# wifi.net
KiCad netlist of a schematic drawn in Altium Designer
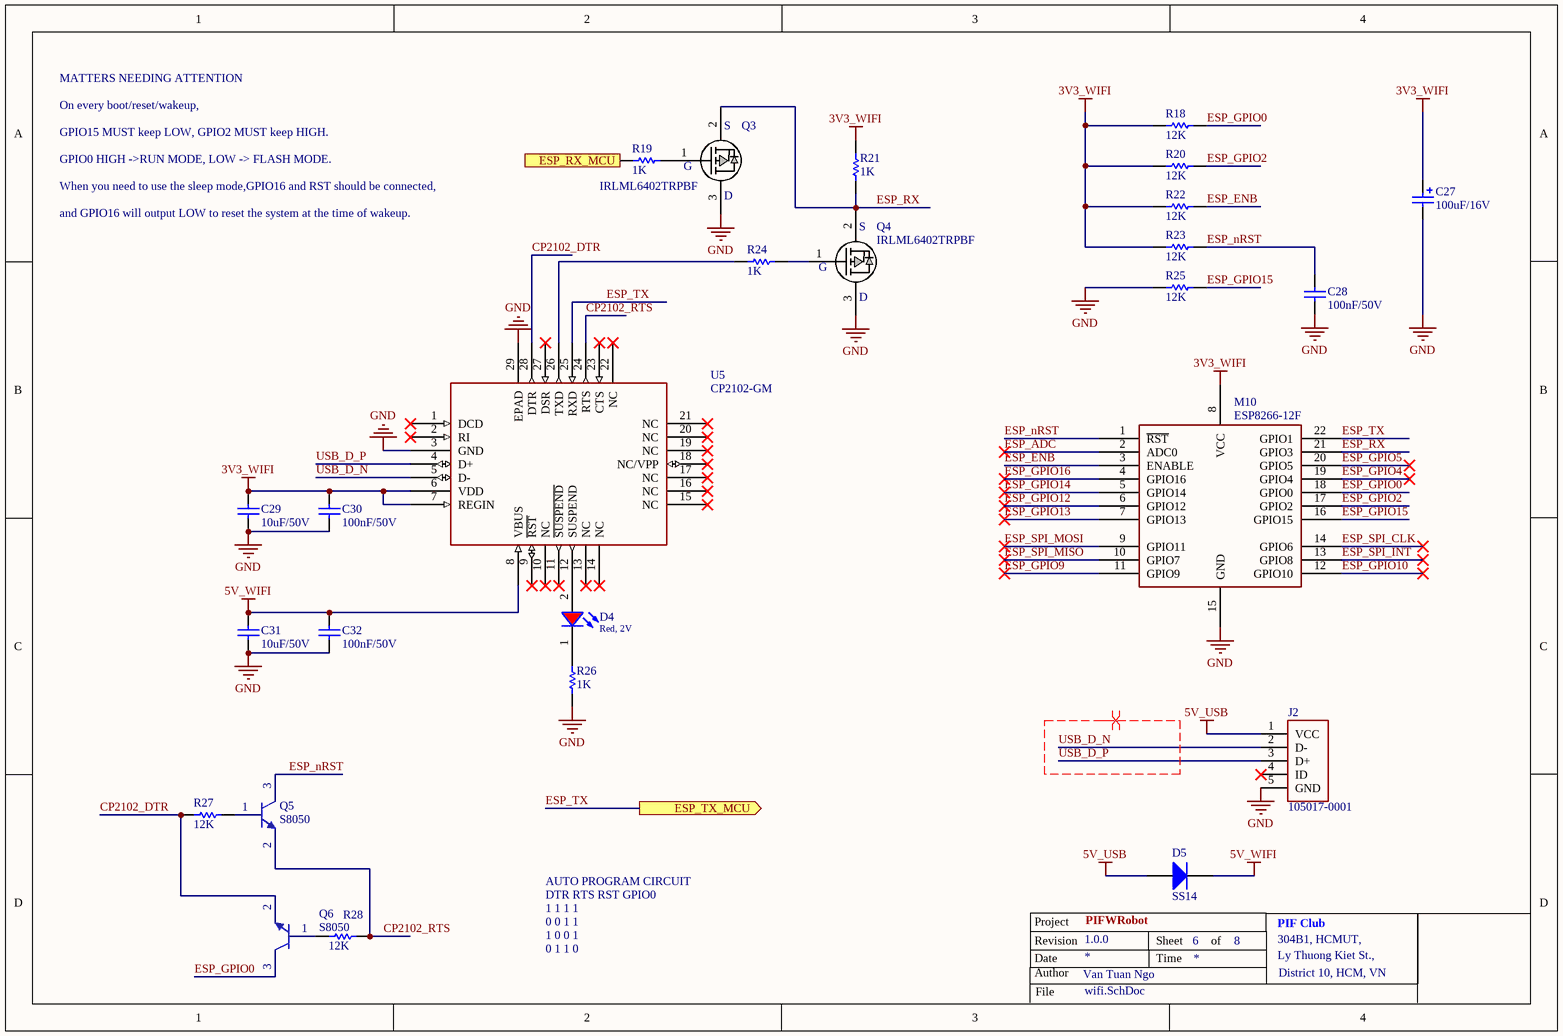
[diagram p0: wifi.SchDoc]

(export (version "E")
  (design (tool "Eeschema 10.0.6"))
  (components
    (comp (ref "C27")
      (value "100uF/16V")
      (footprint "CAP_SM_TAN")
      (fields
        (field (name "MANUFACTURER") "Nichicon")
        (field (name "MANUFACTURER PART NUMBER") "UWX1C101MCL1GB")
        (field (name "Comment") "TAJB107M006RNJ")
      )
      (libsource (lib "Capacitor") (part "Cap-Tan-100uF-16V"))
    )
    (comp (ref "C28")
      (value "100nF/50V")
      (footprint "CAP-SM-0805")
      (description "CAP CER 0.1UF 50V Y5V 0805")
      (fields
        (field (name "MANUFACTURER") "Samsung Electro-Mechanics")
        (field (name "MANUFACTURER PART NUMBER") "CL21F104ZBCNNNC")
      )
      (libsource (lib "Capacitor") (part "Cap-100nF-50V-0805"))
    )
    (comp (ref "C29")
      (value "10uF/50V")
      (footprint "CAP-SM-0805")
      (description "CAP CER 10UF 50V X5R 0805")
      (fields
        (field (name "MANUFACTURER") "Yageo")
        (field (name "MANUFACTURER PART NUMBER") "CC0805KKX5R9BB106")
      )
      (libsource (lib "Capacitor") (part "Cap-10uF-50V-0805"))
    )
    (comp (ref "C30")
      (value "100nF/50V")
      (footprint "CAP-SM-0805")
      (description "CAP CER 0.1UF 50V Y5V 0805")
      (fields
        (field (name "MANUFACTURER") "Samsung Electro-Mechanics")
        (field (name "MANUFACTURER PART NUMBER") "CL21F104ZBCNNNC")
      )
      (libsource (lib "Capacitor") (part "Cap-100nF-50V-0805"))
    )
    (comp (ref "C31")
      (value "10uF/50V")
      (footprint "CAP-SM-0805")
      (description "CAP CER 10UF 50V X5R 0805")
      (fields
        (field (name "MANUFACTURER") "Yageo")
        (field (name "MANUFACTURER PART NUMBER") "CC0805KKX5R9BB106")
      )
      (libsource (lib "Capacitor") (part "Cap-10uF-50V-0805"))
    )
    (comp (ref "C32")
      (value "100nF/50V")
      (footprint "CAP-SM-0805")
      (description "CAP CER 0.1UF 50V Y5V 0805")
      (fields
        (field (name "MANUFACTURER") "Samsung Electro-Mechanics")
        (field (name "MANUFACTURER PART NUMBER") "CL21F104ZBCNNNC")
      )
      (libsource (lib "Capacitor") (part "Cap-100nF-50V-0805"))
    )
    (comp (ref "D4")
      (value "Red, 2V")
      (footprint "WL-SMCW_0805")
      (description "WL-SMCW SMT Mono-color Chip LED Waterclear, size 0805, Red, 2V, 140deg")
      (fields
        (field (name "PART NUMBER") "150080RS75000")
        (field (name "LOCAL SUPPLIER PARTNUMBER") "x")
        (field (name "PUBLISHER") "Wurth Elektronik")
      )
      (libsource (lib "LED") (part "0805-Red"))
    )
    (comp (ref "D5")
      (value "SS14")
      (footprint "SS14")
      (description "DIODE SCHOTTKY 40V 1A SMA")
      (fields (field (name "MANUFACTURER") "ON Semiconductor"))
      (libsource (lib "Diode") (part "Diode-SS14"))
    )
    (comp (ref "J2")
      (value "105017-0001")
      (footprint "CONN_105017-0001")
      (description "CONN RCPT USB2.0 MICRO B SMD R/A")
      (fields
        (field (name "LOCAL SUPPLIER PART NUMBER") "x")
        (field (name "COPYRIGHT") "Copyright (C) 2018 Accelerated Designs. All rights reserved")
      )
      (libsource (lib "Header-Connector") (part "105017-0001"))
    )
    (comp (ref "M10")
      (value "ESP8266-12F")
      (footprint "ESP8266-12F")
      (fields (field (name "LOCAL SUPPLIER PART NUMBER") "x"))
      (libsource (lib "PIFWRobot") (part "ESP8266-12F"))
    )
    (comp (ref "Q3")
      (value "IRLML6402TRPBF")
      (footprint "SOT23_NEX")
      (description "P-Channel 20V 3.7A (Ta) 1.3W (Ta) Surface Mount Micro3™/SOT-23")
      (libsource (lib "MOSFET") (part "IRLML6402TRPBF"))
    )
    (comp (ref "Q4")
      (value "IRLML6402TRPBF")
      (footprint "SOT23_NEX")
      (description "P-Channel 20V 3.7A (Ta) 1.3W (Ta) Surface Mount Micro3™/SOT-23")
      (libsource (lib "MOSFET") (part "IRLML6402TRPBF"))
    )
    (comp (ref "Q5") (value "S8050") (footprint "SOT23_NEX") (libsource (lib "BJT") (part "S8050")))
    (comp (ref "Q6") (value "S8050") (footprint "SOT23_NEX") (libsource (lib "BJT") (part "S8050")))
    (comp (ref "R18")
      (value "12K")
      (footprint "Resistor:RES-SM-0805")
      (description "RES 12 KOHM JUMPER 0805")
      (fields
        (field (name "MANUFACTURER") "Vishay Thin Film")
        (field (name "MANUFACTURER PART NUMBER") "PAT0805E3121BST1")
      )
      (libsource (lib "Resistor") (part "Res-12K-0805"))
    )
    (comp (ref "R19")
      (value "1K")
      (footprint "Resistor:RES-SM-0805")
      (description "RES 1K OHM 1% 1/4W 0805")
      (fields
        (field (name "MANUFACTURER") "Stackpole Electronics Inc")
        (field (name "MANUFACTURER PART NUMBER") "RNCP0805FTD1K00")
      )
      (libsource (lib "Resistor") (part "Res-1K-0805"))
    )
    (comp (ref "R20")
      (value "12K")
      (footprint "Resistor:RES-SM-0805")
      (description "RES 12 KOHM JUMPER 0805")
      (fields
        (field (name "MANUFACTURER") "Vishay Thin Film")
        (field (name "MANUFACTURER PART NUMBER") "PAT0805E3121BST1")
      )
      (libsource (lib "Resistor") (part "Res-12K-0805"))
    )
    (comp (ref "R21")
      (value "1K")
      (footprint "Resistor:RES-SM-0805")
      (description "RES 1K OHM 1% 1/4W 0805")
      (fields
        (field (name "MANUFACTURER") "Stackpole Electronics Inc")
        (field (name "MANUFACTURER PART NUMBER") "RNCP0805FTD1K00")
      )
      (libsource (lib "Resistor") (part "Res-1K-0805"))
    )
    (comp (ref "R22")
      (value "12K")
      (footprint "Resistor:RES-SM-0805")
      (description "RES 12 KOHM JUMPER 0805")
      (fields
        (field (name "MANUFACTURER") "Vishay Thin Film")
        (field (name "MANUFACTURER PART NUMBER") "PAT0805E3121BST1")
      )
      (libsource (lib "Resistor") (part "Res-12K-0805"))
    )
    (comp (ref "R23")
      (value "12K")
      (footprint "Resistor:RES-SM-0805")
      (description "RES 12 KOHM JUMPER 0805")
      (fields
        (field (name "MANUFACTURER") "Vishay Thin Film")
        (field (name "MANUFACTURER PART NUMBER") "PAT0805E3121BST1")
      )
      (libsource (lib "Resistor") (part "Res-12K-0805"))
    )
    (comp (ref "R24")
      (value "1K")
      (footprint "Resistor:RES-SM-0805")
      (description "RES 1K OHM 1% 1/4W 0805")
      (fields
        (field (name "MANUFACTURER") "Stackpole Electronics Inc")
        (field (name "MANUFACTURER PART NUMBER") "RNCP0805FTD1K00")
      )
      (libsource (lib "Resistor") (part "Res-1K-0805"))
    )
    (comp (ref "R25")
      (value "12K")
      (footprint "Resistor:RES-SM-0805")
      (description "RES 12 KOHM JUMPER 0805")
      (fields
        (field (name "MANUFACTURER") "Vishay Thin Film")
        (field (name "MANUFACTURER PART NUMBER") "PAT0805E3121BST1")
      )
      (libsource (lib "Resistor") (part "Res-12K-0805"))
    )
    (comp (ref "R26")
      (value "1K")
      (footprint "Resistor:RES-SM-0805")
      (description "RES 1K OHM 1% 1/4W 0805")
      (fields
        (field (name "MANUFACTURER") "Stackpole Electronics Inc")
        (field (name "MANUFACTURER PART NUMBER") "RNCP0805FTD1K00")
      )
      (libsource (lib "Resistor") (part "Res-1K-0805"))
    )
    (comp (ref "R27")
      (value "12K")
      (footprint "Resistor:RES-SM-0805")
      (description "RES 12 KOHM JUMPER 0805")
      (fields
        (field (name "MANUFACTURER") "Vishay Thin Film")
        (field (name "MANUFACTURER PART NUMBER") "PAT0805E3121BST1")
      )
      (libsource (lib "Resistor") (part "Res-12K-0805"))
    )
    (comp (ref "R28")
      (value "12K")
      (footprint "Resistor:RES-SM-0805")
      (description "RES 12 KOHM JUMPER 0805")
      (fields
        (field (name "MANUFACTURER") "Vishay Thin Film")
        (field (name "MANUFACTURER PART NUMBER") "PAT0805E3121BST1")
      )
      (libsource (lib "Resistor") (part "Res-12K-0805"))
    )
    (comp (ref "U5")
      (value "CP2102-GM")
      (footprint "QFN28_5X5_SIL")
      (fields (field (name "COPYRIGHT") "Copyright (C) 2018 Accelerated Designs. All rights reserved"))
      (libsource (lib "PIFWRobot") (part "CP2102-GM"))
    )
  )
  (nets
    (net (code "1") (name "/CP2102_DTR") (class "Default")
      (node (ref "Q6") (pin "2") (pinfunction "E_2") (pintype "passive"))
      (node (ref "R27") (pin "1") (pinfunction "1_1") (pintype "passive"))
      (node (ref "U5") (pin "28") (pinfunction "DTR_28") (pintype "output"))
    )
    (net (code "2") (name "/CP2102_RTS") (class "Default")
      (node (ref "Q5") (pin "2") (pinfunction "E_2") (pintype "passive"))
      (node (ref "R28") (pin "2") (pinfunction "2_2") (pintype "passive"))
      (node (ref "U5") (pin "24") (pinfunction "RTS_24") (pintype "output"))
    )
    (net (code "3") (name "/ESP_ADC") (class "Default")
      (node (ref "M10") (pin "2") (pinfunction "ADC0_2") (pintype "passive+no_connect"))
    )
    (net (code "4") (name "/ESP_ENB") (class "Default")
      (node (ref "M10") (pin "3") (pinfunction "ENABLE_3") (pintype "passive"))
      (node (ref "R22") (pin "2") (pinfunction "2_2") (pintype "passive"))
    )
    (net (code "5") (name "/ESP_GPIO0") (class "Default")
      (node (ref "M10") (pin "18") (pinfunction "GPIO0_18") (pintype "passive"))
      (node (ref "Q6") (pin "3") (pinfunction "C_3") (pintype "passive"))
      (node (ref "R18") (pin "2") (pinfunction "2_2") (pintype "passive"))
    )
    (net (code "6") (name "/ESP_GPIO2") (class "Default")
      (node (ref "M10") (pin "17") (pinfunction "GPIO2_17") (pintype "passive"))
      (node (ref "R20") (pin "2") (pinfunction "2_2") (pintype "passive"))
    )
    (net (code "7") (name "/ESP_GPIO4") (class "Default")
      (node (ref "M10") (pin "19") (pinfunction "GPIO4_19") (pintype "passive+no_connect"))
    )
    (net (code "8") (name "/ESP_GPIO5") (class "Default")
      (node (ref "M10") (pin "20") (pinfunction "GPIO5_20") (pintype "passive+no_connect"))
    )
    (net (code "9") (name "/ESP_GPIO9") (class "Default")
      (node (ref "M10") (pin "11") (pinfunction "GPIO9_11") (pintype "passive+no_connect"))
    )
    (net (code "10") (name "/ESP_GPIO10") (class "Default")
      (node (ref "M10") (pin "12") (pinfunction "GPIO10_12") (pintype "passive+no_connect"))
    )
    (net (code "11") (name "/ESP_GPIO12") (class "Default")
      (node (ref "M10") (pin "6") (pinfunction "GPIO12_6") (pintype "passive+no_connect"))
    )
    (net (code "12") (name "/ESP_GPIO13") (class "Default")
      (node (ref "M10") (pin "7") (pinfunction "GPIO13_7") (pintype "passive+no_connect"))
    )
    (net (code "13") (name "/ESP_GPIO14") (class "Default")
      (node (ref "M10") (pin "5") (pinfunction "GPIO14_5") (pintype "passive+no_connect"))
    )
    (net (code "14") (name "/ESP_GPIO15") (class "Default")
      (node (ref "M10") (pin "16") (pinfunction "GPIO15_16") (pintype "passive"))
      (node (ref "R25") (pin "2") (pinfunction "2_2") (pintype "passive"))
    )
    (net (code "15") (name "/ESP_GPIO16") (class "Default")
      (node (ref "M10") (pin "4") (pinfunction "GPIO16_4") (pintype "passive+no_connect"))
    )
    (net (code "16") (name "/ESP_RX") (class "Default")
      (node (ref "M10") (pin "21") (pinfunction "GPIO3_21") (pintype "passive"))
      (node (ref "Q3") (pin "2") (pinfunction "S_2") (pintype "passive"))
      (node (ref "Q4") (pin "2") (pinfunction "S_2") (pintype "passive"))
      (node (ref "R21") (pin "1") (pinfunction "1_1") (pintype "passive"))
    )
    (net (code "17") (name "/ESP_RX_MCU") (class "Default")
      (node (ref "R19") (pin "1") (pinfunction "1_1") (pintype "passive"))
    )
    (net (code "18") (name "/ESP_SPI_CLK") (class "Default")
      (node (ref "M10") (pin "14") (pinfunction "GPIO6_14") (pintype "passive+no_connect"))
    )
    (net (code "19") (name "/ESP_SPI_INT") (class "Default")
      (node (ref "M10") (pin "13") (pinfunction "GPIO8_13") (pintype "passive+no_connect"))
    )
    (net (code "20") (name "/ESP_SPI_MISO") (class "Default")
      (node (ref "M10") (pin "10") (pinfunction "GPIO7_10") (pintype "passive+no_connect"))
    )
    (net (code "21") (name "/ESP_SPI_MOSI") (class "Default")
      (node (ref "M10") (pin "9") (pinfunction "GPIO11_9") (pintype "passive+no_connect"))
    )
    (net (code "22") (name "/ESP_TX") (class "Default")
      (node (ref "M10") (pin "22") (pinfunction "GPIO1_22") (pintype "passive"))
      (node (ref "U5") (pin "25") (pinfunction "RXD_25") (pintype "input"))
    )
    (net (code "23") (name "/ESP_nRST") (class "Default")
      (node (ref "C28") (pin "2") (pinfunction "2_2") (pintype "passive"))
      (node (ref "M10") (pin "1") (pinfunction "~{RST}_1") (pintype "passive"))
      (node (ref "Q5") (pin "3") (pinfunction "C_3") (pintype "passive"))
      (node (ref "R23") (pin "2") (pinfunction "2_2") (pintype "passive"))
    )
    (net (code "24") (name "/USB_D_N") (class "Default")
      (node (ref "J2") (pin "2") (pinfunction "D-_2") (pintype "passive"))
      (node (ref "U5") (pin "5") (pinfunction "D-_5") (pintype "bidirectional"))
    )
    (net (code "25") (name "/USB_D_P") (class "Default")
      (node (ref "J2") (pin "3") (pinfunction "D+_3") (pintype "passive"))
      (node (ref "U5") (pin "4") (pinfunction "D+_4") (pintype "bidirectional"))
    )
    (net (code "26") (name "3V3_WIFI") (class "Default")
      (node (ref "C27") (pin "1") (pinfunction "1_1") (pintype "passive"))
      (node (ref "C29") (pin "2") (pinfunction "2_2") (pintype "passive"))
      (node (ref "C30") (pin "2") (pinfunction "2_2") (pintype "passive"))
      (node (ref "M10") (pin "8") (pinfunction "VCC_8") (pintype "passive"))
      (node (ref "R18") (pin "1") (pinfunction "1_1") (pintype "passive"))
      (node (ref "R20") (pin "1") (pinfunction "1_1") (pintype "passive"))
      (node (ref "R21") (pin "2") (pinfunction "2_2") (pintype "passive"))
      (node (ref "R22") (pin "1") (pinfunction "1_1") (pintype "passive"))
      (node (ref "R23") (pin "1") (pinfunction "1_1") (pintype "passive"))
      (node (ref "U5") (pin "6") (pinfunction "VDD_6") (pintype "power_in"))
      (node (ref "U5") (pin "7") (pinfunction "REGIN_7") (pintype "input"))
    )
    (net (code "27") (name "5V_USB") (class "Default")
      (node (ref "D5") (pin "2") (pinfunction "A_2") (pintype "passive"))
      (node (ref "J2") (pin "1") (pinfunction "VCC_1") (pintype "passive"))
    )
    (net (code "28") (name "5V_WIFI") (class "Default")
      (node (ref "C31") (pin "2") (pinfunction "2_2") (pintype "passive"))
      (node (ref "C32") (pin "2") (pinfunction "2_2") (pintype "passive"))
      (node (ref "D5") (pin "1") (pinfunction "K_1") (pintype "passive"))
      (node (ref "U5") (pin "8") (pinfunction "VBUS_8") (pintype "input"))
    )
    (net (code "29") (name "GND") (class "Default")
      (node (ref "C27") (pin "2") (pinfunction "2_2") (pintype "passive"))
      (node (ref "C28") (pin "1") (pinfunction "1_1") (pintype "passive"))
      (node (ref "C29") (pin "1") (pinfunction "1_1") (pintype "passive"))
      (node (ref "C30") (pin "1") (pinfunction "1_1") (pintype "passive"))
      (node (ref "C31") (pin "1") (pinfunction "1_1") (pintype "passive"))
      (node (ref "C32") (pin "1") (pinfunction "1_1") (pintype "passive"))
      (node (ref "J2") (pin "5") (pinfunction "GND_5") (pintype "passive"))
      (node (ref "M10") (pin "15") (pinfunction "GND_15") (pintype "passive"))
      (node (ref "Q3") (pin "3") (pinfunction "D_3") (pintype "passive"))
      (node (ref "Q4") (pin "3") (pinfunction "D_3") (pintype "passive"))
      (node (ref "R25") (pin "1") (pinfunction "1_1") (pintype "passive"))
      (node (ref "R26") (pin "2") (pinfunction "2_2") (pintype "passive"))
      (node (ref "U5") (pin "29") (pinfunction "EPAD_29") (pintype "passive"))
      (node (ref "U5") (pin "3") (pinfunction "GND_3") (pintype "power_in"))
    )
    (net (code "30") (name "Net-(D4-A)") (class "Default")
      (node (ref "D4") (pin "2") (pinfunction "A_2") (pintype "passive"))
      (node (ref "U5") (pin "12") (pinfunction "SUSPEND_12") (pintype "output"))
    )
    (net (code "31") (name "Net-(D4-K)") (class "Default")
      (node (ref "D4") (pin "1") (pinfunction "K_1") (pintype "passive"))
      (node (ref "R26") (pin "1") (pinfunction "1_1") (pintype "passive"))
    )
    (net (code "32") (name "Net-(Q3-G)") (class "Default")
      (node (ref "Q3") (pin "1") (pinfunction "G_1") (pintype "passive"))
      (node (ref "R19") (pin "2") (pinfunction "2_2") (pintype "passive"))
    )
    (net (code "33") (name "Net-(Q4-G)") (class "Default")
      (node (ref "Q4") (pin "1") (pinfunction "G_1") (pintype "passive"))
      (node (ref "R24") (pin "2") (pinfunction "2_2") (pintype "passive"))
    )
    (net (code "34") (name "Net-(Q5-B)") (class "Default")
      (node (ref "Q5") (pin "1") (pinfunction "B_1") (pintype "passive"))
      (node (ref "R27") (pin "2") (pinfunction "2_2") (pintype "passive"))
    )
    (net (code "35") (name "Net-(Q6-B)") (class "Default")
      (node (ref "Q6") (pin "1") (pinfunction "B_1") (pintype "passive"))
      (node (ref "R28") (pin "1") (pinfunction "1_1") (pintype "passive"))
    )
    (net (code "36") (name "Net-(U5-TXD)") (class "Default")
      (node (ref "R24") (pin "1") (pinfunction "1_1") (pintype "passive"))
      (node (ref "U5") (pin "26") (pinfunction "TXD_26") (pintype "output"))
    )
    (net (code "37") (name "unconnected-(J2-ID-Pad4)") (class "Default")
      (node (ref "J2") (pin "4") (pinfunction "ID_4") (pintype "passive+no_connect"))
    )
    (net (code "38") (name "unconnected-(U5-CTS-Pad23)") (class "Default")
      (node (ref "U5") (pin "23") (pinfunction "CTS_23") (pintype "input+no_connect"))
    )
    (net (code "39") (name "unconnected-(U5-DCD-Pad1)") (class "Default")
      (node (ref "U5") (pin "1") (pinfunction "DCD_1") (pintype "input+no_connect"))
    )
    (net (code "40") (name "unconnected-(U5-DSR-Pad27)") (class "Default")
      (node (ref "U5") (pin "27") (pinfunction "DSR_27") (pintype "input+no_connect"))
    )
    (net (code "41") (name "unconnected-(U5-NC-Pad10)") (class "Default")
      (node (ref "U5") (pin "10") (pinfunction "NC_10") (pintype "passive+no_connect"))
    )
    (net (code "42") (name "unconnected-(U5-NC-Pad13)") (class "Default")
      (node (ref "U5") (pin "13") (pinfunction "NC_13") (pintype "passive+no_connect"))
    )
    (net (code "43") (name "unconnected-(U5-NC-Pad14)") (class "Default")
      (node (ref "U5") (pin "14") (pinfunction "NC_14") (pintype "passive+no_connect"))
    )
    (net (code "44") (name "unconnected-(U5-NC-Pad15)") (class "Default")
      (node (ref "U5") (pin "15") (pinfunction "NC_15") (pintype "passive+no_connect"))
    )
    (net (code "45") (name "unconnected-(U5-NC-Pad16)") (class "Default")
      (node (ref "U5") (pin "16") (pinfunction "NC_16") (pintype "passive+no_connect"))
    )
    (net (code "46") (name "unconnected-(U5-NC-Pad17)") (class "Default")
      (node (ref "U5") (pin "17") (pinfunction "NC_17") (pintype "passive+no_connect"))
    )
    (net (code "47") (name "unconnected-(U5-NC-Pad19)") (class "Default")
      (node (ref "U5") (pin "19") (pinfunction "NC_19") (pintype "passive+no_connect"))
    )
    (net (code "48") (name "unconnected-(U5-NC-Pad20)") (class "Default")
      (node (ref "U5") (pin "20") (pinfunction "NC_20") (pintype "passive+no_connect"))
    )
    (net (code "49") (name "unconnected-(U5-NC-Pad21)") (class "Default")
      (node (ref "U5") (pin "21") (pinfunction "NC_21") (pintype "passive+no_connect"))
    )
    (net (code "50") (name "unconnected-(U5-NC-Pad22)") (class "Default")
      (node (ref "U5") (pin "22") (pinfunction "NC_22") (pintype "passive+no_connect"))
    )
    (net (code "51") (name "unconnected-(U5-NC{slash}VPP-Pad18)") (class "Default")
      (node (ref "U5") (pin "18") (pinfunction "NC/VPP_18") (pintype "bidirectional+no_connect"))
    )
    (net (code "52") (name "unconnected-(U5-RI-Pad2)") (class "Default")
      (node (ref "U5") (pin "2") (pinfunction "RI_2") (pintype "input+no_connect"))
    )
    (net (code "53") (name "unconnected-(U5-~{RST}-Pad9)") (class "Default")
      (node (ref "U5") (pin "9") (pinfunction "~{RST}_9") (pintype "bidirectional+no_connect"))
    )
    (net (code "54") (name "unconnected-(U5-~{SUSPEND}-Pad11)") (class "Default")
      (node (ref "U5") (pin "11") (pinfunction "~{SUSPEND}_11") (pintype "output+no_connect"))
    )
  )
)
